# design.net
KiCad netlist of a schematic drawn in Altium Designer
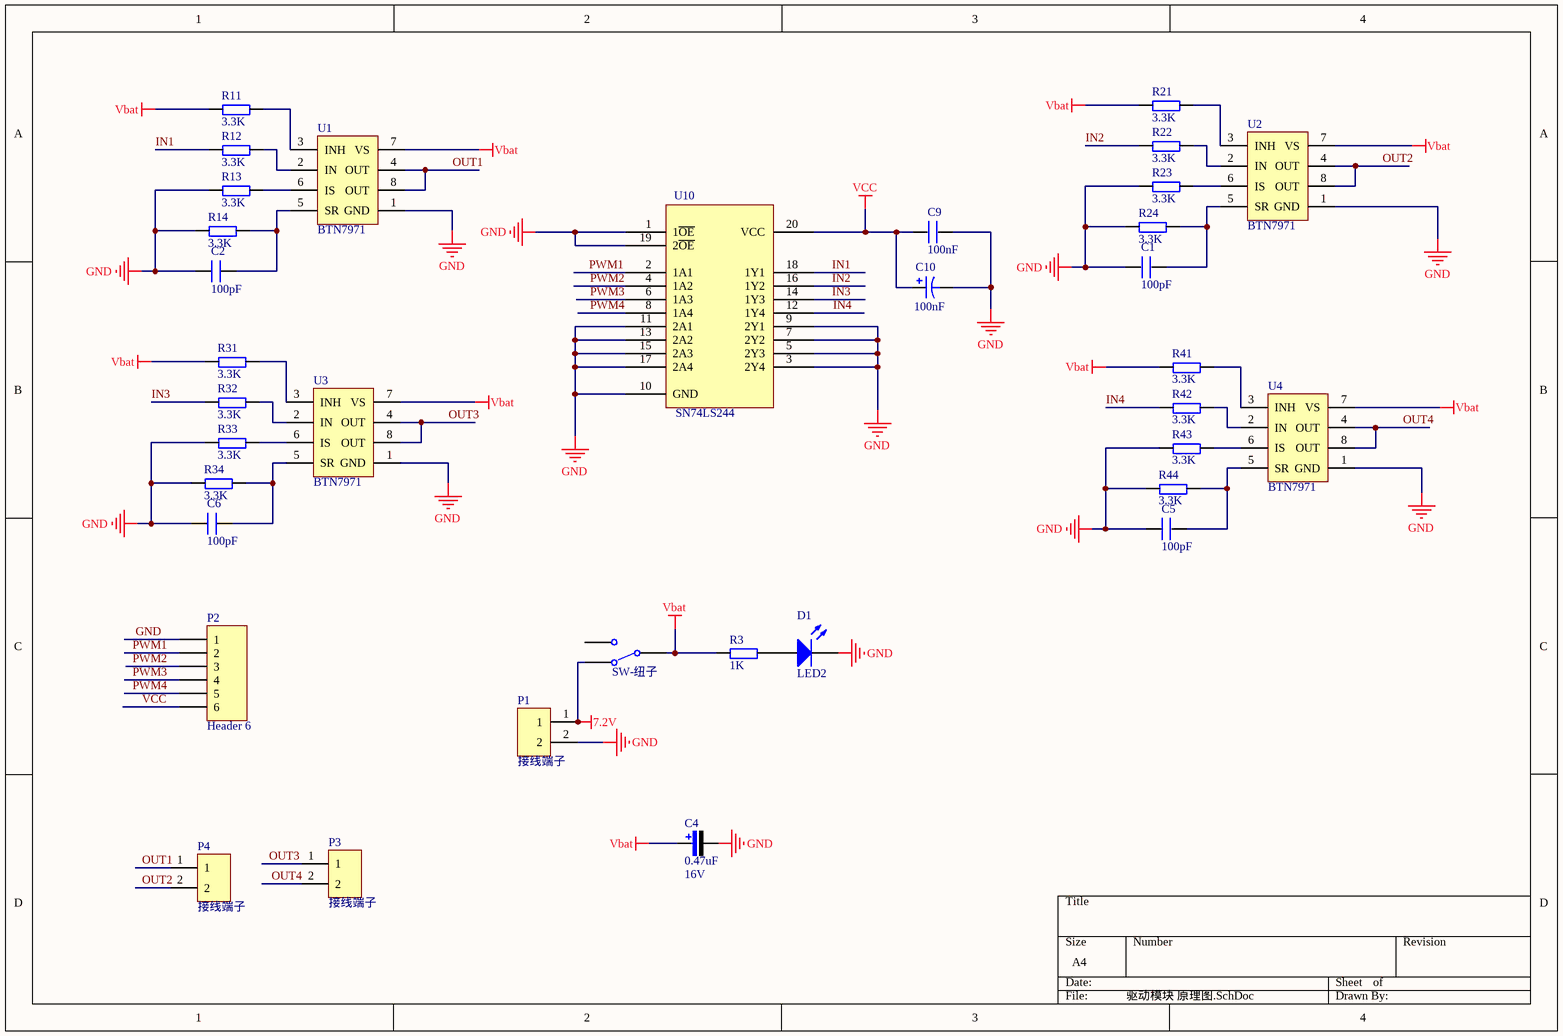
[diagram p0: 驱动模块 原理图.SchDoc]

(export (version "E")
  (design (tool "Eeschema 10.0.6"))
  (components
    (comp (ref "C1") (value "100pF") (footprint "0603") (libsource (lib "辅助元件库") (part "Cap")))
    (comp (ref "C2") (value "100pF") (footprint "0603") (libsource (lib "辅助元件库") (part "Cap")))
    (comp (ref "C4")
      (value "0.47uF")
      (footprint "CAP-3528")
      (description "极性电解电容")
      (fields
        (field (name "VOL") "16V")
        (field (name "Comment") "Cap Pol")
        (field (name "PUBLISHER") "Altium Limited")
      )
      (libsource (lib "Fszhang") (part "Cap Pol"))
    )
    (comp (ref "C5") (value "100pF") (footprint "0603") (libsource (lib "辅助元件库") (part "Cap")))
    (comp (ref "C6") (value "100pF") (footprint "0603") (libsource (lib "辅助元件库") (part "Cap")))
    (comp (ref "C9") (value "100nF") (footprint "0603") (libsource (lib "辅助元件库") (part "Cap")))
    (comp (ref "C10")
      (value "100nF")
      (footprint "CAPC2012L")
      (description "Polarized Capacitor (Surface Mount)")
      (fields (field (name "Comment") "Cap Pol3") (field (name "PUBLISHER") "Altium Limited"))
      (libsource (lib "Miscellaneous Devices") (part "Cap Pol3"))
    )
    (comp (ref "D1")
      (value "LED2")
      (footprint "DSO-F2/D6.1")
      (description "Typical RED, GREEN, YELLOW, AMBER GaAs LED")
      (fields (field (name "PUBLISHER") "Altium Limited"))
      (libsource (lib "Miscellaneous Devices") (part "LED2"))
    )
    (comp (ref "P1") (value "接线端子") (footprint "接线端子") (libsource (lib "") (part "接线端子_1")))
    (comp (ref "P2")
      (value "Header 6")
      (footprint "HDR1X6")
      (description "Header, 6-Pin")
      (fields (field (name "PUBLISHER") "Altium Limited"))
      (libsource (lib "Miscellaneous Connectors") (part "Header 6"))
    )
    (comp (ref "P3") (value "接线端子") (footprint "接线端子") (libsource (lib "辅助元件库") (part "接线端子")))
    (comp (ref "P4") (value "接线端子") (footprint "接线端子") (libsource (lib "辅助元件库") (part "接线端子")))
    (comp (ref "R3") (value "1K") (footprint "0603") (libsource (lib "辅助元件库") (part "R")))
    (comp (ref "R11") (value "3.3K") (footprint "0603") (libsource (lib "辅助元件库") (part "R")))
    (comp (ref "R12") (value "3.3K") (footprint "0603") (libsource (lib "辅助元件库") (part "R")))
    (comp (ref "R13") (value "3.3K") (footprint "0603") (libsource (lib "辅助元件库") (part "R")))
    (comp (ref "R14") (value "3.3K") (footprint "0603") (libsource (lib "辅助元件库") (part "R")))
    (comp (ref "R21") (value "3.3K") (footprint "0603") (libsource (lib "辅助元件库") (part "R")))
    (comp (ref "R22") (value "3.3K") (footprint "0603") (libsource (lib "辅助元件库") (part "R")))
    (comp (ref "R23") (value "3.3K") (footprint "0603") (libsource (lib "辅助元件库") (part "R")))
    (comp (ref "R24") (value "3.3K") (footprint "0603") (libsource (lib "辅助元件库") (part "R")))
    (comp (ref "R31") (value "3.3K") (footprint "0603") (libsource (lib "辅助元件库") (part "R")))
    (comp (ref "R32") (value "3.3K") (footprint "0603") (libsource (lib "辅助元件库") (part "R")))
    (comp (ref "R33") (value "3.3K") (footprint "0603") (libsource (lib "辅助元件库") (part "R")))
    (comp (ref "R34") (value "3.3K") (footprint "0603") (libsource (lib "辅助元件库") (part "R")))
    (comp (ref "R41") (value "3.3K") (footprint "0603") (libsource (lib "辅助元件库") (part "R")))
    (comp (ref "R42") (value "3.3K") (footprint "0603") (libsource (lib "辅助元件库") (part "R")))
    (comp (ref "R43") (value "3.3K") (footprint "0603") (libsource (lib "辅助元件库") (part "R")))
    (comp (ref "R44") (value "3.3K") (footprint "0603") (libsource (lib "辅助元件库") (part "R")))
    (comp (ref "SW1") (value "SW-纽子") (footprint "SW-纽子") (libsource (lib "辅助元件库") (part "SW-纽子")))
    (comp (ref "U1") (value "BTN7971") (footprint "BTN7971") (libsource (lib "辅助元件库") (part "BTN7971")))
    (comp (ref "U2") (value "BTN7971") (footprint "BTN7971") (libsource (lib "辅助元件库") (part "BTN7971")))
    (comp (ref "U3") (value "BTN7971") (footprint "BTN7971") (libsource (lib "辅助元件库") (part "BTN7971")))
    (comp (ref "U4") (value "BTN7971") (footprint "BTN7971") (libsource (lib "辅助元件库") (part "BTN7971")))
    (comp (ref "U10")
      (value "SN74LS244")
      (footprint "SN74LS244")
      (libsource (lib "bei_Schlib1") (part "SN74LS244"))
    )
  )
  (nets
    (net (code "1") (name "/IN1") (class "Default")
      (node (ref "R12") (pin "1") (pintype "passive"))
      (node (ref "U10") (pin "18") (pinfunction "1Y1_18") (pintype "passive"))
    )
    (net (code "2") (name "/IN2") (class "Default")
      (node (ref "R22") (pin "1") (pintype "passive"))
      (node (ref "U10") (pin "16") (pinfunction "1Y2_16") (pintype "passive"))
    )
    (net (code "3") (name "/IN3") (class "Default")
      (node (ref "R32") (pin "1") (pintype "passive"))
      (node (ref "U10") (pin "14") (pinfunction "1Y3_14") (pintype "passive"))
    )
    (net (code "4") (name "/IN4") (class "Default")
      (node (ref "R42") (pin "1") (pintype "passive"))
      (node (ref "U10") (pin "12") (pinfunction "1Y4_12") (pintype "passive"))
    )
    (net (code "5") (name "/OUT1") (class "Default")
      (node (ref "P4") (pin "1") (pinfunction "1_1") (pintype "open_collector"))
      (node (ref "U1") (pin "4") (pinfunction "OUT_4") (pintype "open_collector"))
      (node (ref "U1") (pin "8") (pinfunction "OUT_8") (pintype "open_collector"))
    )
    (net (code "6") (name "/OUT2") (class "Default")
      (node (ref "P4") (pin "2") (pinfunction "2_2") (pintype "open_collector"))
      (node (ref "U2") (pin "4") (pinfunction "OUT_4") (pintype "open_collector"))
      (node (ref "U2") (pin "8") (pinfunction "OUT_8") (pintype "open_collector"))
    )
    (net (code "7") (name "/OUT3") (class "Default")
      (node (ref "P3") (pin "1") (pinfunction "1_1") (pintype "open_collector"))
      (node (ref "U3") (pin "4") (pinfunction "OUT_4") (pintype "open_collector"))
      (node (ref "U3") (pin "8") (pinfunction "OUT_8") (pintype "open_collector"))
    )
    (net (code "8") (name "/OUT4") (class "Default")
      (node (ref "P3") (pin "2") (pinfunction "2_2") (pintype "open_collector"))
      (node (ref "U4") (pin "4") (pinfunction "OUT_4") (pintype "open_collector"))
      (node (ref "U4") (pin "8") (pinfunction "OUT_8") (pintype "open_collector"))
    )
    (net (code "9") (name "/PWM1") (class "Default")
      (node (ref "P2") (pin "2") (pinfunction "2_2") (pintype "passive"))
      (node (ref "U10") (pin "2") (pinfunction "1A1_2") (pintype "passive"))
    )
    (net (code "10") (name "/PWM2") (class "Default")
      (node (ref "P2") (pin "3") (pinfunction "3_3") (pintype "passive"))
      (node (ref "U10") (pin "4") (pinfunction "1A2_4") (pintype "passive"))
    )
    (net (code "11") (name "/PWM3") (class "Default")
      (node (ref "P2") (pin "4") (pinfunction "4_4") (pintype "passive"))
      (node (ref "U10") (pin "6") (pinfunction "1A3_6") (pintype "passive"))
    )
    (net (code "12") (name "/PWM4") (class "Default")
      (node (ref "P2") (pin "5") (pinfunction "5_5") (pintype "passive"))
      (node (ref "U10") (pin "8") (pinfunction "1A4_8") (pintype "passive"))
    )
    (net (code "13") (name "7.2V") (class "Default")
      (node (ref "P1") (pin "1") (pinfunction "1_1") (pintype "open_collector"))
      (node (ref "SW1") (pin "1") (pinfunction "NO_1") (pintype "passive"))
    )
    (net (code "14") (name "GND") (class "Default")
      (node (ref "C1") (pin "1") (pintype "passive"))
      (node (ref "C10") (pin "2") (pinfunction "2_2") (pintype "passive"))
      (node (ref "C2") (pin "1") (pintype "passive"))
      (node (ref "C4") (pin "2") (pinfunction "2_2") (pintype "passive"))
      (node (ref "C5") (pin "1") (pintype "passive"))
      (node (ref "C6") (pin "1") (pintype "passive"))
      (node (ref "C9") (pin "2") (pintype "passive"))
      (node (ref "D1") (pin "2") (pinfunction "K_2") (pintype "passive"))
      (node (ref "P1") (pin "2") (pinfunction "2_2") (pintype "open_collector"))
      (node (ref "P2") (pin "1") (pinfunction "1_1") (pintype "passive"))
      (node (ref "R13") (pin "1") (pintype "passive"))
      (node (ref "R14") (pin "1") (pintype "passive"))
      (node (ref "R23") (pin "1") (pintype "passive"))
      (node (ref "R24") (pin "1") (pintype "passive"))
      (node (ref "R33") (pin "1") (pintype "passive"))
      (node (ref "R34") (pin "1") (pintype "passive"))
      (node (ref "R43") (pin "1") (pintype "passive"))
      (node (ref "R44") (pin "1") (pintype "passive"))
      (node (ref "U1") (pin "1") (pinfunction "GND_1") (pintype "open_collector"))
      (node (ref "U10") (pin "1") (pinfunction "1~{OE}_1") (pintype "passive"))
      (node (ref "U10") (pin "10") (pinfunction "GND_10") (pintype "passive"))
      (node (ref "U10") (pin "11") (pinfunction "2A1_11") (pintype "passive"))
      (node (ref "U10") (pin "13") (pinfunction "2A2_13") (pintype "passive"))
      (node (ref "U10") (pin "15") (pinfunction "2A3_15") (pintype "passive"))
      (node (ref "U10") (pin "17") (pinfunction "2A4_17") (pintype "passive"))
      (node (ref "U10") (pin "19") (pinfunction "2~{OE}_19") (pintype "passive"))
      (node (ref "U10") (pin "3") (pinfunction "2Y4_3") (pintype "passive"))
      (node (ref "U10") (pin "5") (pinfunction "2Y3_5") (pintype "passive"))
      (node (ref "U10") (pin "7") (pinfunction "2Y2_7") (pintype "passive"))
      (node (ref "U10") (pin "9") (pinfunction "2Y1_9") (pintype "passive"))
      (node (ref "U2") (pin "1") (pinfunction "GND_1") (pintype "open_collector"))
      (node (ref "U3") (pin "1") (pinfunction "GND_1") (pintype "open_collector"))
      (node (ref "U4") (pin "1") (pinfunction "GND_1") (pintype "open_collector"))
    )
    (net (code "15") (name "Net-(D1-A)") (class "Default")
      (node (ref "D1") (pin "1") (pinfunction "A_1") (pintype "passive"))
      (node (ref "R3") (pin "2") (pintype "passive"))
    )
    (net (code "16") (name "Net-(U1-IN)") (class "Default")
      (node (ref "R12") (pin "2") (pintype "passive"))
      (node (ref "U1") (pin "2") (pinfunction "IN_2") (pintype "open_collector"))
    )
    (net (code "17") (name "Net-(U1-INH)") (class "Default")
      (node (ref "R11") (pin "2") (pintype "passive"))
      (node (ref "U1") (pin "3") (pinfunction "INH_3") (pintype "open_collector"))
    )
    (net (code "18") (name "Net-(U1-IS)") (class "Default")
      (node (ref "R13") (pin "2") (pintype "passive"))
      (node (ref "U1") (pin "6") (pinfunction "IS_6") (pintype "open_collector"))
    )
    (net (code "19") (name "Net-(U1-SR)") (class "Default")
      (node (ref "C2") (pin "2") (pintype "passive"))
      (node (ref "R14") (pin "2") (pintype "passive"))
      (node (ref "U1") (pin "5") (pinfunction "SR_5") (pintype "open_collector"))
    )
    (net (code "20") (name "Net-(U2-IN)") (class "Default")
      (node (ref "R22") (pin "2") (pintype "passive"))
      (node (ref "U2") (pin "2") (pinfunction "IN_2") (pintype "open_collector"))
    )
    (net (code "21") (name "Net-(U2-INH)") (class "Default")
      (node (ref "R21") (pin "2") (pintype "passive"))
      (node (ref "U2") (pin "3") (pinfunction "INH_3") (pintype "open_collector"))
    )
    (net (code "22") (name "Net-(U2-IS)") (class "Default")
      (node (ref "R23") (pin "2") (pintype "passive"))
      (node (ref "U2") (pin "6") (pinfunction "IS_6") (pintype "open_collector"))
    )
    (net (code "23") (name "Net-(U2-SR)") (class "Default")
      (node (ref "C1") (pin "2") (pintype "passive"))
      (node (ref "R24") (pin "2") (pintype "passive"))
      (node (ref "U2") (pin "5") (pinfunction "SR_5") (pintype "open_collector"))
    )
    (net (code "24") (name "Net-(U3-IN)") (class "Default")
      (node (ref "R32") (pin "2") (pintype "passive"))
      (node (ref "U3") (pin "2") (pinfunction "IN_2") (pintype "open_collector"))
    )
    (net (code "25") (name "Net-(U3-INH)") (class "Default")
      (node (ref "R31") (pin "2") (pintype "passive"))
      (node (ref "U3") (pin "3") (pinfunction "INH_3") (pintype "open_collector"))
    )
    (net (code "26") (name "Net-(U3-IS)") (class "Default")
      (node (ref "R33") (pin "2") (pintype "passive"))
      (node (ref "U3") (pin "6") (pinfunction "IS_6") (pintype "open_collector"))
    )
    (net (code "27") (name "Net-(U3-SR)") (class "Default")
      (node (ref "C6") (pin "2") (pintype "passive"))
      (node (ref "R34") (pin "2") (pintype "passive"))
      (node (ref "U3") (pin "5") (pinfunction "SR_5") (pintype "open_collector"))
    )
    (net (code "28") (name "Net-(U4-IN)") (class "Default")
      (node (ref "R42") (pin "2") (pintype "passive"))
      (node (ref "U4") (pin "2") (pinfunction "IN_2") (pintype "open_collector"))
    )
    (net (code "29") (name "Net-(U4-INH)") (class "Default")
      (node (ref "R41") (pin "2") (pintype "passive"))
      (node (ref "U4") (pin "3") (pinfunction "INH_3") (pintype "open_collector"))
    )
    (net (code "30") (name "Net-(U4-IS)") (class "Default")
      (node (ref "R43") (pin "2") (pintype "passive"))
      (node (ref "U4") (pin "6") (pinfunction "IS_6") (pintype "open_collector"))
    )
    (net (code "31") (name "Net-(U4-SR)") (class "Default")
      (node (ref "C5") (pin "2") (pintype "passive"))
      (node (ref "R44") (pin "2") (pintype "passive"))
      (node (ref "U4") (pin "5") (pinfunction "SR_5") (pintype "open_collector"))
    )
    (net (code "32") (name "VCC") (class "Default")
      (node (ref "C10") (pin "1") (pinfunction "1_1") (pintype "passive"))
      (node (ref "C9") (pin "1") (pintype "passive"))
      (node (ref "P2") (pin "6") (pinfunction "6_6") (pintype "passive"))
      (node (ref "U10") (pin "20") (pinfunction "VCC_20") (pintype "passive"))
    )
    (net (code "33") (name "Vbat") (class "Default")
      (node (ref "C4") (pin "1") (pinfunction "1_1") (pintype "passive"))
      (node (ref "R11") (pin "1") (pintype "passive"))
      (node (ref "R21") (pin "1") (pintype "passive"))
      (node (ref "R3") (pin "1") (pintype "passive"))
      (node (ref "R31") (pin "1") (pintype "passive"))
      (node (ref "R41") (pin "1") (pintype "passive"))
      (node (ref "SW1") (pin "2") (pinfunction "COMMON_2") (pintype "passive"))
      (node (ref "U1") (pin "7") (pinfunction "VS_7") (pintype "open_collector"))
      (node (ref "U2") (pin "7") (pinfunction "VS_7") (pintype "open_collector"))
      (node (ref "U3") (pin "7") (pinfunction "VS_7") (pintype "open_collector"))
      (node (ref "U4") (pin "7") (pinfunction "VS_7") (pintype "open_collector"))
    )
    (net (code "34") (name "unconnected-(SW1-OFF-Pad3)") (class "Default")
      (node (ref "SW1") (pin "3") (pinfunction "OFF_3") (pintype "passive"))
    )
  )
)
